# a-tiny-tractor.net
KiCad netlist of a schematic drawn in EAGLE
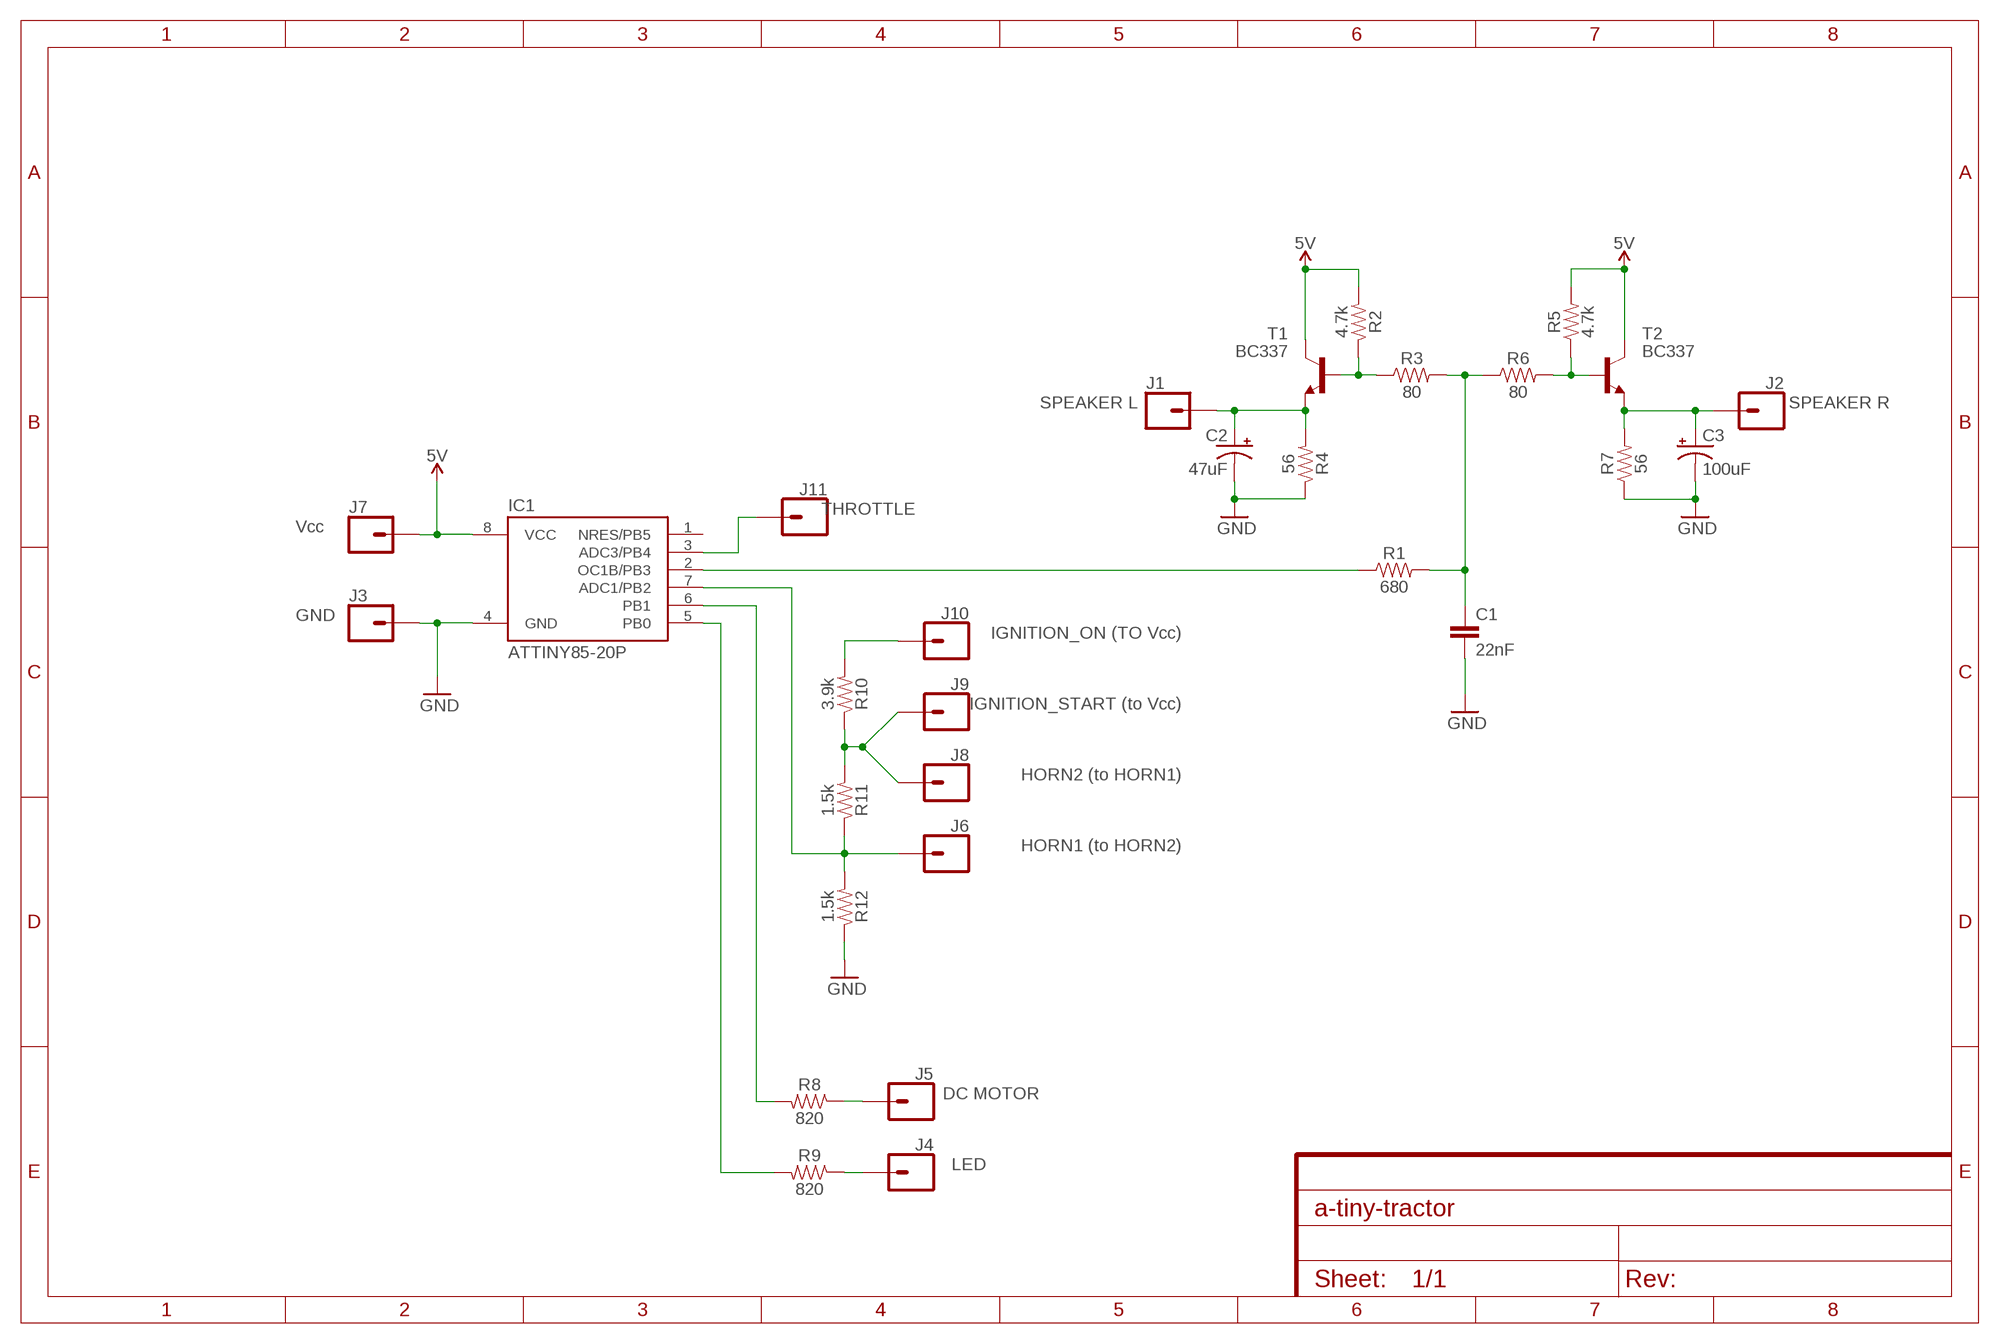
[diagram p0: schematic, sheet 1]

(export (version "E")
  (design (tool "Eeschema 10.0.6"))
  (components
    (comp (ref "C1")
      (value "22nF")
      (footprint "eagle-import:CAP-PTH-10MM")
      (libsource (lib "eagle-import") (part "10NF-PTH-10MM-10000V-1-%"))
    )
    (comp (ref "C2")
      (value "47uF")
      (footprint "eagle-import:CPOL-RADIAL-2.5MM-5MM")
      (libsource (lib "eagle-import") (part "10UF-POLAR-RADIAL-2.5MM-25V-20%"))
    )
    (comp (ref "C3")
      (value "100uF")
      (footprint "eagle-import:CPOL-RADIAL-2.5MM-5MM")
      (libsource (lib "eagle-import") (part "10UF-POLAR-RADIAL-2.5MM-25V-20%"))
    )
    (comp (ref "IC1")
      (value "ATTINY85-20P")
      (footprint "eagle-import:PDIP08_300MIL")
      (libsource (lib "eagle-import") (part "ATTINY85P-20"))
    )
    (comp (ref "J1")
      (value "SPEAKER L")
      (footprint "eagle-import:1X01")
      (libsource (lib "eagle-import") (part "CONN_01"))
    )
    (comp (ref "J2")
      (value "SPEAKER R")
      (footprint "eagle-import:1X01")
      (libsource (lib "eagle-import") (part "CONN_01"))
    )
    (comp (ref "J3")
      (value "GND")
      (footprint "eagle-import:1X01")
      (libsource (lib "eagle-import") (part "CONN_01"))
    )
    (comp (ref "J4")
      (value "LED")
      (footprint "eagle-import:1X01")
      (libsource (lib "eagle-import") (part "CONN_01"))
    )
    (comp (ref "J5")
      (value "DC MOTOR")
      (footprint "eagle-import:1X01")
      (libsource (lib "eagle-import") (part "CONN_01"))
    )
    (comp (ref "J6")
      (value "HORN1 (to HORN2)")
      (footprint "eagle-import:1X01")
      (libsource (lib "eagle-import") (part "CONN_01"))
    )
    (comp (ref "J7")
      (value "Vcc")
      (footprint "eagle-import:1X01")
      (libsource (lib "eagle-import") (part "CONN_01"))
    )
    (comp (ref "J8")
      (value "HORN2 (to HORN1)")
      (footprint "eagle-import:1X01")
      (libsource (lib "eagle-import") (part "CONN_01"))
    )
    (comp (ref "J9")
      (value "IGNITION_START (to Vcc)")
      (footprint "eagle-import:1X01")
      (libsource (lib "eagle-import") (part "CONN_01"))
    )
    (comp (ref "J10")
      (value "IGNITION_ON (TO Vcc)")
      (footprint "eagle-import:1X01")
      (libsource (lib "eagle-import") (part "CONN_01"))
    )
    (comp (ref "J11")
      (value "THROTTLE")
      (footprint "eagle-import:1X01")
      (libsource (lib "eagle-import") (part "CONN_01"))
    )
    (comp (ref "R1")
      (value "680")
      (footprint "eagle-import:AXIAL-0.3")
      (libsource (lib "eagle-import") (part "1KOHM-HORIZ-1/4W-5%"))
    )
    (comp (ref "R2")
      (value "4.7k")
      (footprint "eagle-import:AXIAL-0.3")
      (libsource (lib "eagle-import") (part "1KOHM-HORIZ-1/4W-5%"))
    )
    (comp (ref "R3")
      (value "80")
      (footprint "eagle-import:AXIAL-0.3")
      (libsource (lib "eagle-import") (part "1KOHM-HORIZ-1/4W-5%"))
    )
    (comp (ref "R4")
      (value "56")
      (footprint "eagle-import:AXIAL-0.3")
      (libsource (lib "eagle-import") (part "1KOHM-HORIZ-1/4W-5%"))
    )
    (comp (ref "R5")
      (value "4.7k")
      (footprint "eagle-import:AXIAL-0.3")
      (libsource (lib "eagle-import") (part "1KOHM-HORIZ-1/4W-5%"))
    )
    (comp (ref "R6")
      (value "80")
      (footprint "eagle-import:AXIAL-0.3")
      (libsource (lib "eagle-import") (part "1KOHM-HORIZ-1/4W-5%"))
    )
    (comp (ref "R7")
      (value "56")
      (footprint "eagle-import:AXIAL-0.3")
      (libsource (lib "eagle-import") (part "1KOHM-HORIZ-1/4W-5%"))
    )
    (comp (ref "R8")
      (value "820")
      (footprint "eagle-import:AXIAL-0.3")
      (libsource (lib "eagle-import") (part "1KOHM-HORIZ-1/4W-5%"))
    )
    (comp (ref "R9")
      (value "820")
      (footprint "eagle-import:AXIAL-0.3")
      (libsource (lib "eagle-import") (part "1KOHM-HORIZ-1/4W-5%"))
    )
    (comp (ref "R10")
      (value "3.9k")
      (footprint "eagle-import:AXIAL-0.3")
      (libsource (lib "eagle-import") (part "1KOHM-HORIZ-1/4W-5%"))
    )
    (comp (ref "R11")
      (value "1.5k")
      (footprint "eagle-import:AXIAL-0.3")
      (libsource (lib "eagle-import") (part "1KOHM-HORIZ-1/4W-5%"))
    )
    (comp (ref "R12")
      (value "1.5k")
      (footprint "eagle-import:AXIAL-0.3")
      (libsource (lib "eagle-import") (part "1KOHM-HORIZ-1/4W-5%"))
    )
    (comp (ref "T1")
      (value "BC337")
      (footprint "eagle-import:TO92")
      (libsource (lib "eagle-import") (part "BC337"))
    )
    (comp (ref "T2")
      (value "BC337")
      (footprint "eagle-import:TO92")
      (libsource (lib "eagle-import") (part "BC337"))
    )
  )
  (nets
    (net (code "1") (name "5V") (class "Default")
      (node (ref "IC1") (pin "8") (pinfunction "VCC_8") (pintype "power_in"))
      (node (ref "J7") (pin "1") (pinfunction "1_1") (pintype "passive"))
      (node (ref "R2") (pin "P$2") (pinfunction "2_P$2") (pintype "passive"))
      (node (ref "R5") (pin "P$2") (pinfunction "2_P$2") (pintype "passive"))
      (node (ref "T1") (pin "3") (pinfunction "C_3") (pintype "passive"))
      (node (ref "T2") (pin "3") (pinfunction "C_3") (pintype "passive"))
    )
    (net (code "2") (name "GND") (class "Default")
      (node (ref "C1") (pin "2") (pinfunction "2_2") (pintype "passive"))
      (node (ref "C2") (pin "2") (pinfunction "-_2") (pintype "passive"))
      (node (ref "C3") (pin "2") (pinfunction "-_2") (pintype "passive"))
      (node (ref "IC1") (pin "4") (pinfunction "GND_4") (pintype "power_in"))
      (node (ref "J3") (pin "1") (pinfunction "1_1") (pintype "passive"))
      (node (ref "R12") (pin "P$1") (pinfunction "1_P$1") (pintype "passive"))
      (node (ref "R4") (pin "P$1") (pinfunction "1_P$1") (pintype "passive"))
      (node (ref "R7") (pin "P$1") (pinfunction "1_P$1") (pintype "passive"))
    )
    (net (code "3") (name "Net-(C2-+)") (class "Default")
      (node (ref "C2") (pin "1") (pinfunction "+_1") (pintype "passive"))
      (node (ref "J1") (pin "1") (pinfunction "1_1") (pintype "passive"))
      (node (ref "R4") (pin "P$2") (pinfunction "2_P$2") (pintype "passive"))
      (node (ref "T1") (pin "1") (pinfunction "E_1") (pintype "passive"))
    )
    (net (code "4") (name "Net-(C3-+)") (class "Default")
      (node (ref "C3") (pin "1") (pinfunction "+_1") (pintype "passive"))
      (node (ref "J2") (pin "1") (pinfunction "1_1") (pintype "passive"))
      (node (ref "R7") (pin "P$2") (pinfunction "2_P$2") (pintype "passive"))
      (node (ref "T2") (pin "1") (pinfunction "E_1") (pintype "passive"))
    )
    (net (code "5") (name "Net-(IC1-ADC1{slash}PB2)") (class "Default")
      (node (ref "IC1") (pin "7") (pinfunction "ADC1/PB2_7") (pintype "bidirectional"))
      (node (ref "J6") (pin "1") (pinfunction "1_1") (pintype "passive"))
      (node (ref "R11") (pin "P$1") (pinfunction "1_P$1") (pintype "passive"))
      (node (ref "R12") (pin "P$2") (pinfunction "2_P$2") (pintype "passive"))
    )
    (net (code "6") (name "Net-(IC1-ADC3{slash}PB4)") (class "Default")
      (node (ref "IC1") (pin "3") (pinfunction "ADC3/PB4_3") (pintype "bidirectional"))
      (node (ref "J11") (pin "1") (pinfunction "1_1") (pintype "passive"))
    )
    (net (code "7") (name "Net-(IC1-OC1B{slash}PB3)") (class "Default")
      (node (ref "IC1") (pin "2") (pinfunction "OC1B/PB3_2") (pintype "bidirectional"))
      (node (ref "R1") (pin "P$1") (pinfunction "1_P$1") (pintype "passive"))
    )
    (net (code "8") (name "Net-(IC1-PB0)") (class "Default")
      (node (ref "IC1") (pin "5") (pinfunction "PB0_5") (pintype "bidirectional"))
      (node (ref "R9") (pin "P$2") (pinfunction "2_P$2") (pintype "passive"))
    )
    (net (code "9") (name "Net-(IC1-PB1)") (class "Default")
      (node (ref "IC1") (pin "6") (pinfunction "PB1_6") (pintype "bidirectional"))
      (node (ref "R8") (pin "P$2") (pinfunction "2_P$2") (pintype "passive"))
    )
    (net (code "10") (name "Net-(R1-2)") (class "Default")
      (node (ref "C1") (pin "1") (pinfunction "1_1") (pintype "passive"))
      (node (ref "R1") (pin "P$2") (pinfunction "2_P$2") (pintype "passive"))
      (node (ref "R3") (pin "P$2") (pinfunction "2_P$2") (pintype "passive"))
      (node (ref "R6") (pin "P$1") (pinfunction "1_P$1") (pintype "passive"))
    )
    (net (code "11") (name "Net-(R2-1)") (class "Default")
      (node (ref "R2") (pin "P$1") (pinfunction "1_P$1") (pintype "passive"))
      (node (ref "R3") (pin "P$1") (pinfunction "1_P$1") (pintype "passive"))
      (node (ref "T1") (pin "2") (pinfunction "B_2") (pintype "passive"))
    )
    (net (code "12") (name "Net-(R5-1)") (class "Default")
      (node (ref "R5") (pin "P$1") (pinfunction "1_P$1") (pintype "passive"))
      (node (ref "R6") (pin "P$2") (pinfunction "2_P$2") (pintype "passive"))
      (node (ref "T2") (pin "2") (pinfunction "B_2") (pintype "passive"))
    )
    (net (code "13") (name "Net-(R8-1)") (class "Default")
      (node (ref "J5") (pin "1") (pinfunction "1_1") (pintype "passive"))
      (node (ref "R8") (pin "P$1") (pinfunction "1_P$1") (pintype "passive"))
    )
    (net (code "14") (name "Net-(R9-1)") (class "Default")
      (node (ref "J4") (pin "1") (pinfunction "1_1") (pintype "passive"))
      (node (ref "R9") (pin "P$1") (pinfunction "1_P$1") (pintype "passive"))
    )
    (net (code "15") (name "Net-(R10-1)") (class "Default")
      (node (ref "J8") (pin "1") (pinfunction "1_1") (pintype "passive"))
      (node (ref "J9") (pin "1") (pinfunction "1_1") (pintype "passive"))
      (node (ref "R10") (pin "P$1") (pinfunction "1_P$1") (pintype "passive"))
      (node (ref "R11") (pin "P$2") (pinfunction "2_P$2") (pintype "passive"))
    )
    (net (code "16") (name "Net-(R10-2)") (class "Default")
      (node (ref "J10") (pin "1") (pinfunction "1_1") (pintype "passive"))
      (node (ref "R10") (pin "P$2") (pinfunction "2_P$2") (pintype "passive"))
    )
    (net (code "17") (name "unconnected-(IC1-NRES{slash}PB5-Pad1)") (class "Default")
      (node (ref "IC1") (pin "1") (pinfunction "NRES/PB5_1") (pintype "bidirectional"))
    )
  )
)
